# Pyboard_XBee_Skin.net
KiCad netlist of a schematic drawn in EAGLE
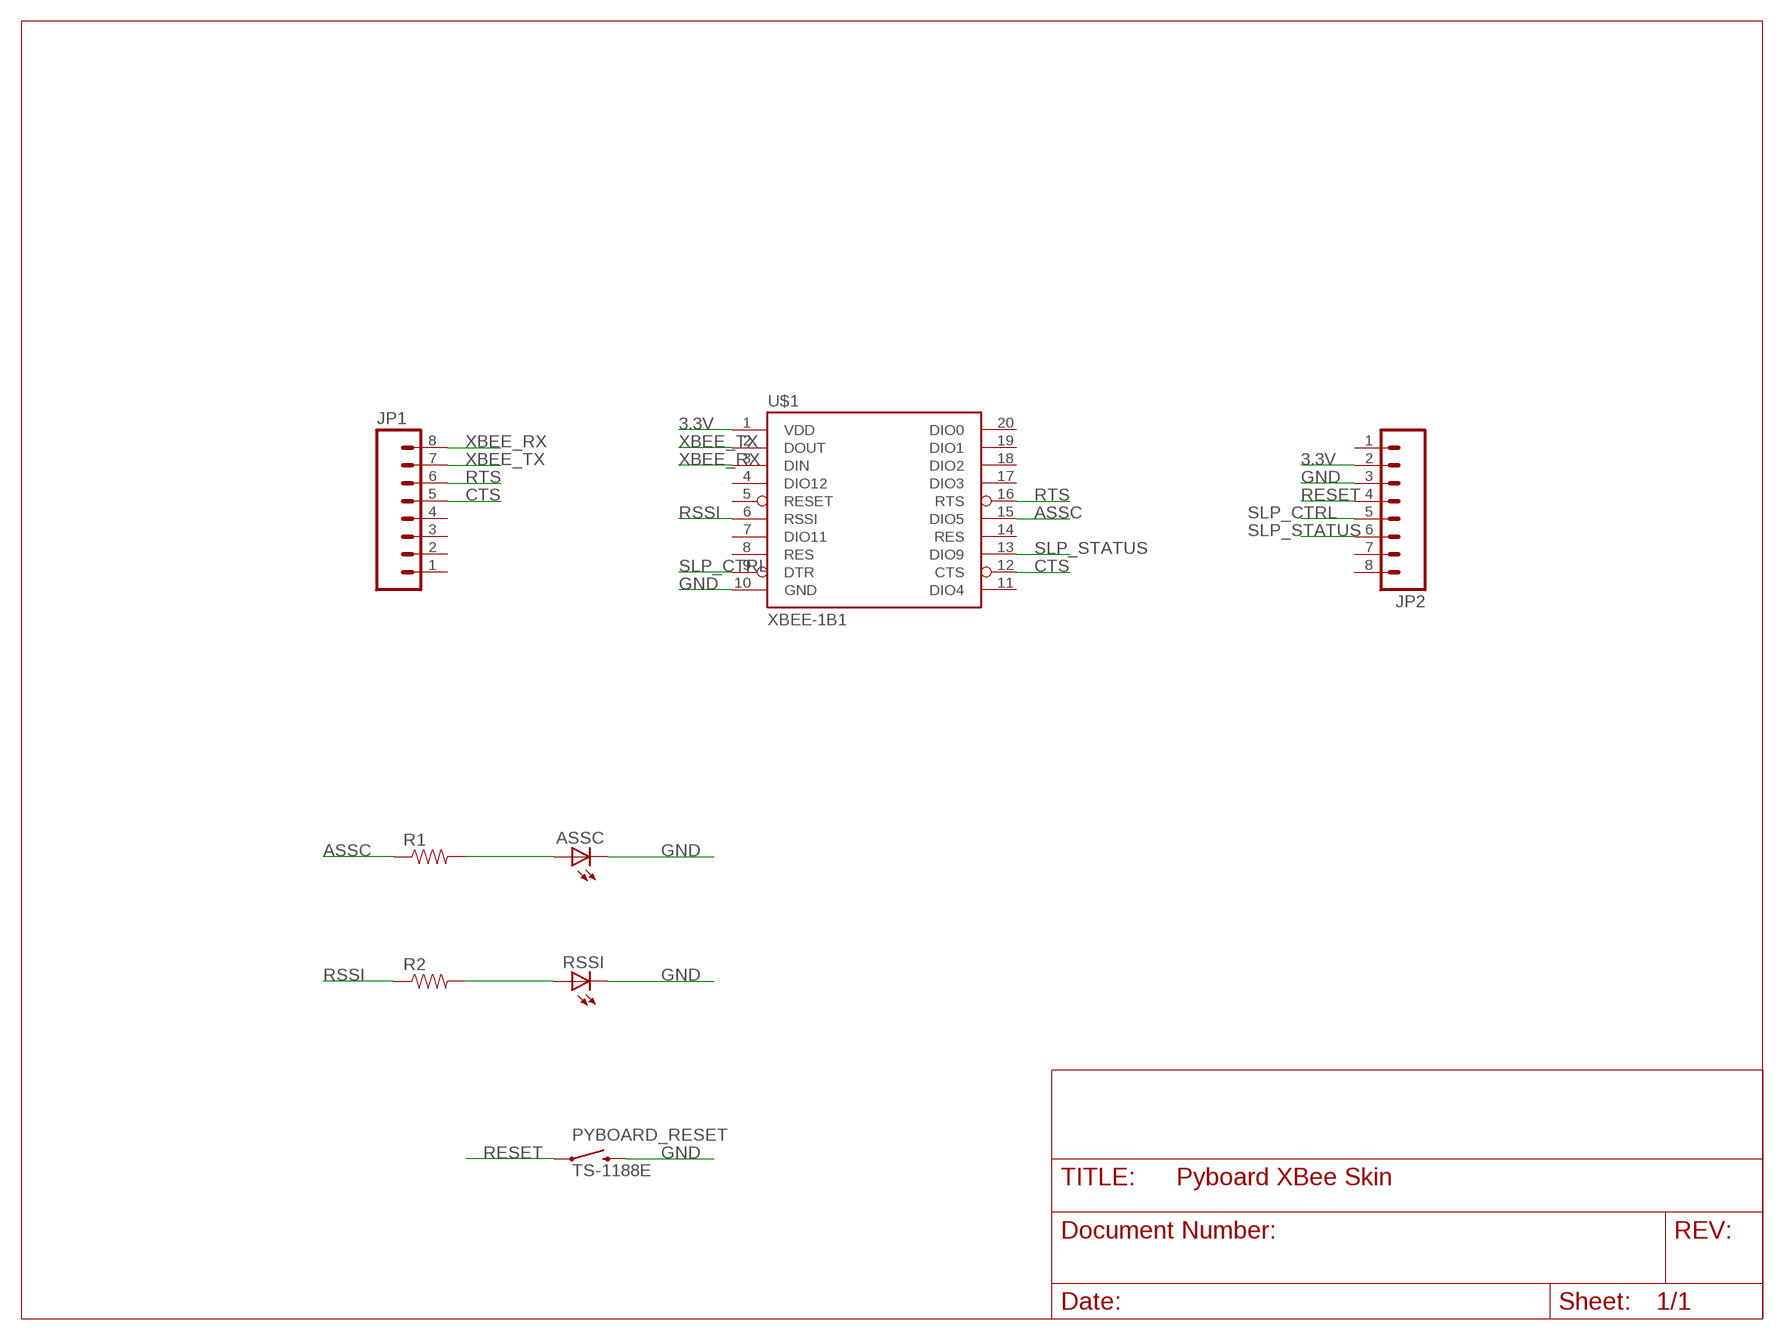
[diagram p0: schematic, sheet 1]

(export (version "E")
  (design (tool "Eeschema 10.0.6"))
  (components
    (comp (ref "ASSC")
      (value "LED0603")
      (footprint "eagle-import:LED-0603")
      (libsource (lib "eagle-import") (part "LED0603"))
    )
    (comp (ref "JP1")
      (value "M081X08")
      (footprint "eagle-import:1X08")
      (libsource (lib "eagle-import") (part "M081X08"))
    )
    (comp (ref "JP2")
      (value "M081X08")
      (footprint "eagle-import:1X08")
      (libsource (lib "eagle-import") (part "M081X08"))
    )
    (comp (ref "PYBOARD_RESET")
      (value "TS-1188E")
      (footprint "eagle-import:TACTILE_SWITCH_SMD")
      (libsource (lib "eagle-import") (part "SWITCH-MOMENTARY-2SMD"))
    )
    (comp (ref "R1")
      (value "RESISTOR0603-RES")
      (footprint "eagle-import:0603-RES")
      (libsource (lib "eagle-import") (part "RESISTOR0603-RES"))
    )
    (comp (ref "R2")
      (value "RESISTOR0603-RES")
      (footprint "eagle-import:0603-RES")
      (libsource (lib "eagle-import") (part "RESISTOR0603-RES"))
    )
    (comp (ref "RSSI")
      (value "LED0603")
      (footprint "eagle-import:LED-0603")
      (libsource (lib "eagle-import") (part "LED0603"))
    )
    (comp (ref "U$1")
      (value "XBEE-1B1")
      (footprint "eagle-import:XBEE-1")
      (libsource (lib "eagle-import") (part "XBEE-1B1"))
    )
  )
  (nets
    (net (code "1") (name "/3.3V") (class "Default")
      (node (ref "JP2") (pin "2") (pinfunction "2_2") (pintype "passive"))
      (node (ref "U$1") (pin "1") (pinfunction "VDD_1") (pintype "power_in"))
    )
    (net (code "2") (name "/ASSC") (class "Default")
      (node (ref "R1") (pin "1") (pinfunction "1_1") (pintype "passive"))
      (node (ref "U$1") (pin "15") (pinfunction "DIO5_15") (pintype "bidirectional"))
    )
    (net (code "3") (name "/CTS") (class "Default")
      (node (ref "JP1") (pin "5") (pinfunction "5_5") (pintype "passive"))
      (node (ref "U$1") (pin "12") (pinfunction "CTS_12") (pintype "output"))
    )
    (net (code "4") (name "/GND") (class "Default")
      (node (ref "ASSC") (pin "C") (pinfunction "C_C") (pintype "passive"))
      (node (ref "JP2") (pin "3") (pinfunction "3_3") (pintype "passive"))
      (node (ref "PYBOARD_RESET") (pin "3") (pinfunction "2_3") (pintype "passive"))
      (node (ref "RSSI") (pin "C") (pinfunction "C_C") (pintype "passive"))
      (node (ref "U$1") (pin "10") (pinfunction "GND_10") (pintype "power_in"))
    )
    (net (code "5") (name "/RESET") (class "Default")
      (node (ref "JP2") (pin "4") (pinfunction "4_4") (pintype "passive"))
      (node (ref "PYBOARD_RESET") (pin "1") (pinfunction "1_1") (pintype "passive"))
    )
    (net (code "6") (name "/RSSI") (class "Default")
      (node (ref "R2") (pin "1") (pinfunction "1_1") (pintype "passive"))
      (node (ref "U$1") (pin "6") (pinfunction "RSSI_6") (pintype "bidirectional"))
    )
    (net (code "7") (name "/RTS") (class "Default")
      (node (ref "JP1") (pin "6") (pinfunction "6_6") (pintype "passive"))
      (node (ref "U$1") (pin "16") (pinfunction "RTS_16") (pintype "input"))
    )
    (net (code "8") (name "/SLP_CTRL") (class "Default")
      (node (ref "JP2") (pin "5") (pinfunction "5_5") (pintype "passive"))
      (node (ref "U$1") (pin "9") (pinfunction "DTR_9") (pintype "bidirectional"))
    )
    (net (code "9") (name "/SLP_STATUS") (class "Default")
      (node (ref "JP2") (pin "6") (pinfunction "6_6") (pintype "passive"))
      (node (ref "U$1") (pin "13") (pinfunction "DIO9_13") (pintype "bidirectional"))
    )
    (net (code "10") (name "/XBEE_RX") (class "Default")
      (node (ref "JP1") (pin "8") (pinfunction "8_8") (pintype "passive"))
      (node (ref "U$1") (pin "3") (pinfunction "DIN_3") (pintype "input"))
    )
    (net (code "11") (name "/XBEE_TX") (class "Default")
      (node (ref "JP1") (pin "7") (pinfunction "7_7") (pintype "passive"))
      (node (ref "U$1") (pin "2") (pinfunction "DOUT_2") (pintype "output"))
    )
    (net (code "12") (name "Net-(ASSC-PadA)") (class "Default")
      (node (ref "ASSC") (pin "A") (pinfunction "A_A") (pintype "passive"))
      (node (ref "R1") (pin "2") (pinfunction "2_2") (pintype "passive"))
    )
    (net (code "13") (name "Net-(R2-Pad2)") (class "Default")
      (node (ref "R2") (pin "2") (pinfunction "2_2") (pintype "passive"))
      (node (ref "RSSI") (pin "A") (pinfunction "A_A") (pintype "passive"))
    )
    (net (code "14") (name "unconnected-(JP1-Pad1)") (class "Default")
      (node (ref "JP1") (pin "1") (pinfunction "1_1") (pintype "passive"))
    )
    (net (code "15") (name "unconnected-(JP1-Pad2)") (class "Default")
      (node (ref "JP1") (pin "2") (pinfunction "2_2") (pintype "passive"))
    )
    (net (code "16") (name "unconnected-(JP1-Pad3)") (class "Default")
      (node (ref "JP1") (pin "3") (pinfunction "3_3") (pintype "passive"))
    )
    (net (code "17") (name "unconnected-(JP1-Pad4)") (class "Default")
      (node (ref "JP1") (pin "4") (pinfunction "4_4") (pintype "passive"))
    )
    (net (code "18") (name "unconnected-(JP2-Pad1)") (class "Default")
      (node (ref "JP2") (pin "1") (pinfunction "1_1") (pintype "passive"))
    )
    (net (code "19") (name "unconnected-(JP2-Pad7)") (class "Default")
      (node (ref "JP2") (pin "7") (pinfunction "7_7") (pintype "passive"))
    )
    (net (code "20") (name "unconnected-(JP2-Pad8)") (class "Default")
      (node (ref "JP2") (pin "8") (pinfunction "8_8") (pintype "passive"))
    )
    (net (code "21") (name "unconnected-(U$1-DIO0-Pad20)") (class "Default")
      (node (ref "U$1") (pin "20") (pinfunction "DIO0_20") (pintype "bidirectional"))
    )
    (net (code "22") (name "unconnected-(U$1-DIO1-Pad19)") (class "Default")
      (node (ref "U$1") (pin "19") (pinfunction "DIO1_19") (pintype "bidirectional"))
    )
    (net (code "23") (name "unconnected-(U$1-DIO2-Pad18)") (class "Default")
      (node (ref "U$1") (pin "18") (pinfunction "DIO2_18") (pintype "bidirectional"))
    )
    (net (code "24") (name "unconnected-(U$1-DIO3-Pad17)") (class "Default")
      (node (ref "U$1") (pin "17") (pinfunction "DIO3_17") (pintype "bidirectional"))
    )
    (net (code "25") (name "unconnected-(U$1-DIO4-Pad11)") (class "Default")
      (node (ref "U$1") (pin "11") (pinfunction "DIO4_11") (pintype "bidirectional"))
    )
    (net (code "26") (name "unconnected-(U$1-DIO11-Pad7)") (class "Default")
      (node (ref "U$1") (pin "7") (pinfunction "DIO11_7") (pintype "bidirectional"))
    )
    (net (code "27") (name "unconnected-(U$1-DIO12-Pad4)") (class "Default")
      (node (ref "U$1") (pin "4") (pinfunction "DIO12_4") (pintype "bidirectional"))
    )
    (net (code "28") (name "unconnected-(U$1-RES-Pad8)") (class "Default")
      (node (ref "U$1") (pin "8") (pinfunction "RES_8") (pintype "bidirectional"))
    )
    (net (code "29") (name "unconnected-(U$1-RES-Pad14)") (class "Default")
      (node (ref "U$1") (pin "14") (pinfunction "RES_14") (pintype "bidirectional"))
    )
    (net (code "30") (name "unconnected-(U$1-RESET-Pad5)") (class "Default")
      (node (ref "U$1") (pin "5") (pinfunction "RESET_5") (pintype "input"))
    )
  )
)
